# Multiplier.net
KiCad netlist of a schematic drawn in EAGLE
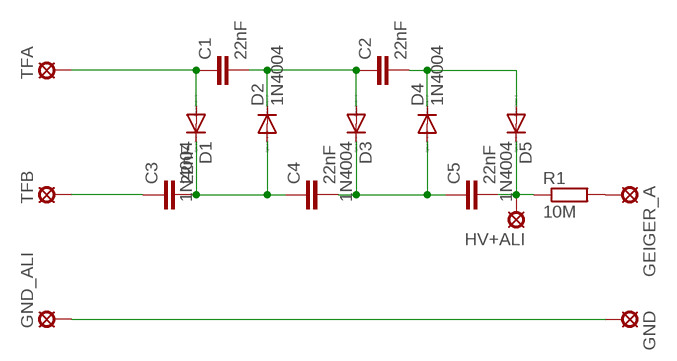
[diagram p0: schematic, sheet 1]

(export (version "E")
  (design (tool "Eeschema 10.0.6"))
  (components
    (comp (ref "C1")
      (value "22nF")
      (footprint "eagle-import:C025_050-025X075")
      (libsource (lib "eagle-import") (part "C-EU025_050-025X075"))
    )
    (comp (ref "C2")
      (value "22nF")
      (footprint "eagle-import:C025_050-025X075")
      (libsource (lib "eagle-import") (part "C-EU025_050-025X075"))
    )
    (comp (ref "C3")
      (value "22nF")
      (footprint "eagle-import:C025_050-025X075")
      (libsource (lib "eagle-import") (part "C-EU025_050-025X075"))
    )
    (comp (ref "C4")
      (value "22nF")
      (footprint "eagle-import:C025_050-025X075")
      (libsource (lib "eagle-import") (part "C-EU025_050-025X075"))
    )
    (comp (ref "C5")
      (value "22nF")
      (footprint "eagle-import:C025_050-025X075")
      (libsource (lib "eagle-import") (part "C-EU025_050-025X075"))
    )
    (comp (ref "D1")
      (value "1N4004")
      (footprint "eagle-import:DO41-10")
      (libsource (lib "eagle-import") (part "1N4004"))
    )
    (comp (ref "D2")
      (value "1N4004")
      (footprint "eagle-import:DO41-10")
      (libsource (lib "eagle-import") (part "1N4004"))
    )
    (comp (ref "D3")
      (value "1N4004")
      (footprint "eagle-import:DO41-10")
      (libsource (lib "eagle-import") (part "1N4004"))
    )
    (comp (ref "D4")
      (value "1N4004")
      (footprint "eagle-import:DO41-10")
      (libsource (lib "eagle-import") (part "1N4004"))
    )
    (comp (ref "D5")
      (value "1N4004")
      (footprint "eagle-import:DO41-10")
      (libsource (lib "eagle-import") (part "1N4004"))
    )
    (comp (ref "GEIGER_A")
      (value "LSP10")
      (footprint "eagle-import:LSP10")
      (libsource (lib "eagle-import") (part "LSP10"))
    )
    (comp (ref "GND")
      (value "LSP10")
      (footprint "eagle-import:LSP10")
      (libsource (lib "eagle-import") (part "LSP10"))
    )
    (comp (ref "GND_ALI")
      (value "LSP10")
      (footprint "eagle-import:LSP10")
      (libsource (lib "eagle-import") (part "LSP10"))
    )
    (comp (ref "HV+ALI")
      (value "LSP10")
      (footprint "eagle-import:LSP10")
      (libsource (lib "eagle-import") (part "LSP10"))
    )
    (comp (ref "R1")
      (value "10M")
      (footprint "eagle-import:0309_10")
      (libsource (lib "eagle-import") (part "R-EU_0309/10"))
    )
    (comp (ref "TFA")
      (value "LSP10")
      (footprint "eagle-import:LSP10")
      (libsource (lib "eagle-import") (part "LSP10"))
    )
    (comp (ref "TFB")
      (value "LSP10")
      (footprint "eagle-import:LSP10")
      (libsource (lib "eagle-import") (part "LSP10"))
    )
  )
  (nets
    (net (code "1") (name "Net-(C1-Pad1)") (class "Default")
      (node (ref "C1") (pin "1") (pinfunction "1_1") (pintype "passive"))
      (node (ref "D1") (pin "A") (pinfunction "A_A") (pintype "passive"))
      (node (ref "TFA") (pin "MP") (pinfunction "MP_MP") (pintype "passive"))
    )
    (net (code "2") (name "Net-(C1-Pad2)") (class "Default")
      (node (ref "C1") (pin "2") (pinfunction "2_2") (pintype "passive"))
      (node (ref "C2") (pin "1") (pinfunction "1_1") (pintype "passive"))
      (node (ref "D2") (pin "C") (pinfunction "C_C") (pintype "passive"))
      (node (ref "D3") (pin "A") (pinfunction "A_A") (pintype "passive"))
    )
    (net (code "3") (name "Net-(C2-Pad2)") (class "Default")
      (node (ref "C2") (pin "2") (pinfunction "2_2") (pintype "passive"))
      (node (ref "D4") (pin "C") (pinfunction "C_C") (pintype "passive"))
      (node (ref "D5") (pin "A") (pinfunction "A_A") (pintype "passive"))
    )
    (net (code "4") (name "Net-(C3-Pad1)") (class "Default")
      (node (ref "C3") (pin "1") (pinfunction "1_1") (pintype "passive"))
      (node (ref "TFB") (pin "MP") (pinfunction "MP_MP") (pintype "passive"))
    )
    (net (code "5") (name "Net-(C3-Pad2)") (class "Default")
      (node (ref "C3") (pin "2") (pinfunction "2_2") (pintype "passive"))
      (node (ref "C4") (pin "1") (pinfunction "1_1") (pintype "passive"))
      (node (ref "D1") (pin "C") (pinfunction "C_C") (pintype "passive"))
      (node (ref "D2") (pin "A") (pinfunction "A_A") (pintype "passive"))
    )
    (net (code "6") (name "Net-(C4-Pad2)") (class "Default")
      (node (ref "C4") (pin "2") (pinfunction "2_2") (pintype "passive"))
      (node (ref "C5") (pin "1") (pinfunction "1_1") (pintype "passive"))
      (node (ref "D3") (pin "C") (pinfunction "C_C") (pintype "passive"))
      (node (ref "D4") (pin "A") (pinfunction "A_A") (pintype "passive"))
    )
    (net (code "7") (name "Net-(C5-Pad2)") (class "Default")
      (node (ref "C5") (pin "2") (pinfunction "2_2") (pintype "passive"))
      (node (ref "D5") (pin "C") (pinfunction "C_C") (pintype "passive"))
      (node (ref "HV+ALI") (pin "MP") (pinfunction "MP_MP") (pintype "passive"))
      (node (ref "R1") (pin "1") (pinfunction "1_1") (pintype "passive"))
    )
    (net (code "8") (name "Net-(GEIGER_A-PadMP)") (class "Default")
      (node (ref "GEIGER_A") (pin "MP") (pinfunction "MP_MP") (pintype "passive"))
      (node (ref "R1") (pin "2") (pinfunction "2_2") (pintype "passive"))
    )
    (net (code "9") (name "Net-(GND-PadMP)") (class "Default")
      (node (ref "GND") (pin "MP") (pinfunction "MP_MP") (pintype "passive"))
      (node (ref "GND_ALI") (pin "MP") (pinfunction "MP_MP") (pintype "passive"))
    )
  )
)
